# CPLD.net
KiCad netlist of a schematic drawn in Altium Designer
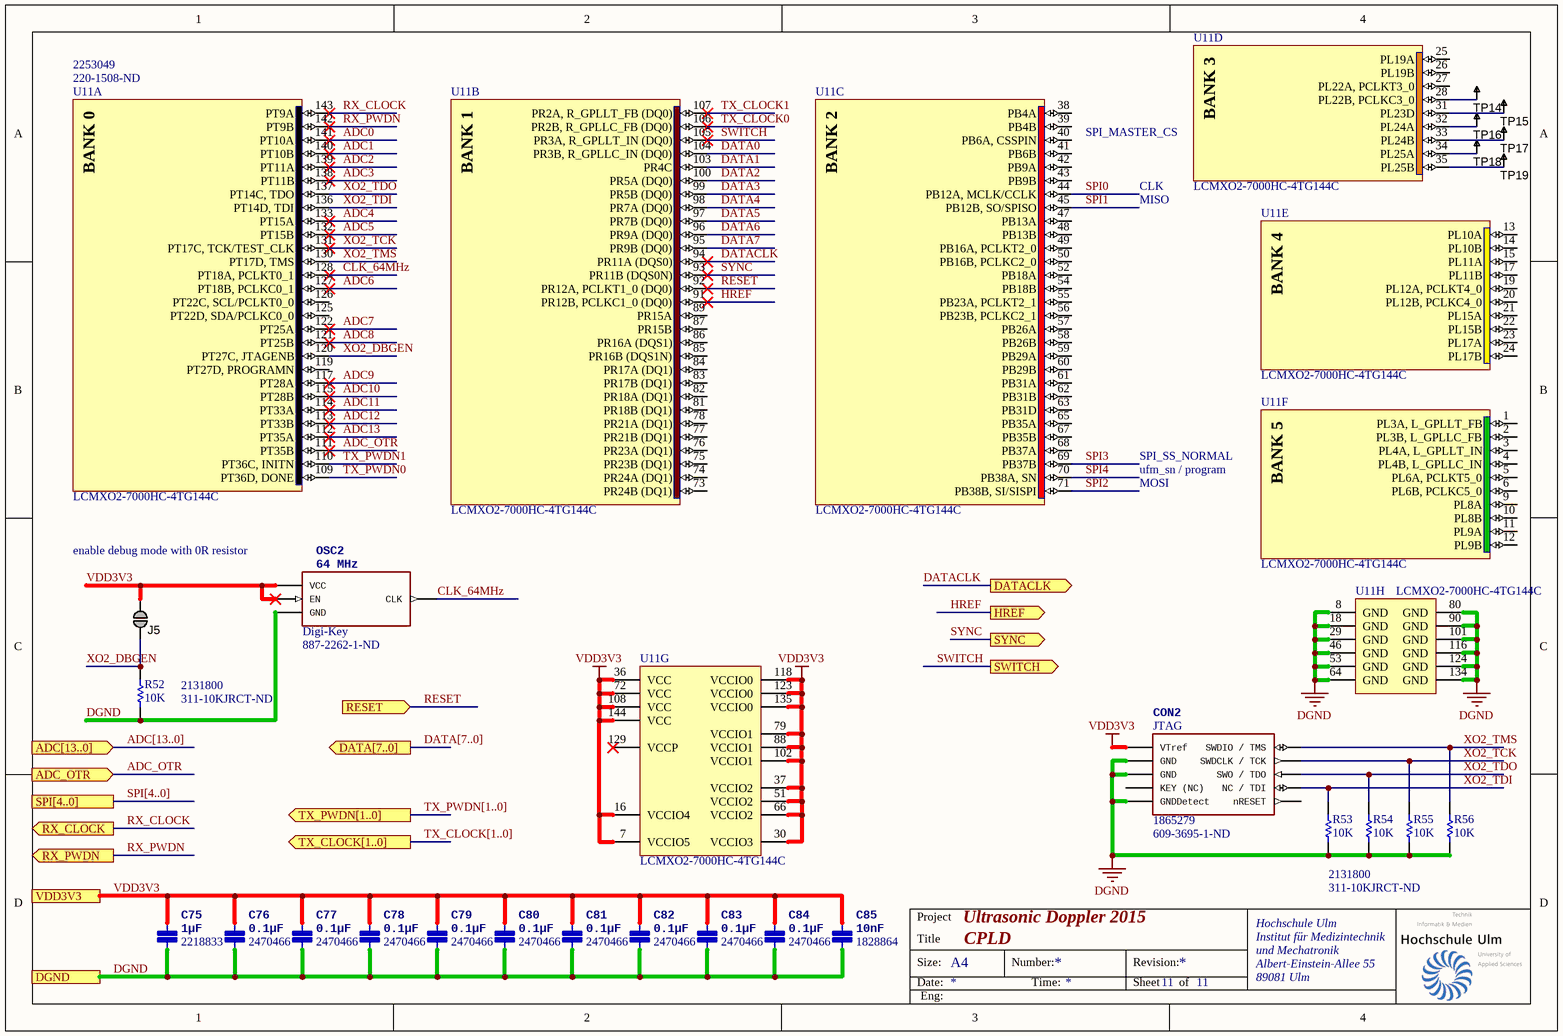
[diagram p0: CPLD.SchDoc]

(export (version "E")
  (design (tool "Eeschema 10.0.6"))
  (components
    (comp (ref "C75")
      (value "1µF")
      (footprint "0402[1005]")
      (description "Cap")
      (fields (field (name "SUPPLIER PART NUMBER 1") "2218833"))
      (libsource (lib "Components") (part "Capacitor"))
    )
    (comp (ref "C76")
      (value "0.1µF")
      (footprint "0402[1005]")
      (description "Cap")
      (fields (field (name "SUPPLIER PART NUMBER 1") "2470466"))
      (libsource (lib "Components") (part "Capacitor"))
    )
    (comp (ref "C77")
      (value "0.1µF")
      (footprint "0402[1005]")
      (description "Cap")
      (fields (field (name "SUPPLIER PART NUMBER 1") "2470466"))
      (libsource (lib "Components") (part "Capacitor"))
    )
    (comp (ref "C78")
      (value "0.1µF")
      (footprint "0402[1005]")
      (description "Cap")
      (fields (field (name "SUPPLIER PART NUMBER 1") "2470466"))
      (libsource (lib "Components") (part "Capacitor"))
    )
    (comp (ref "C79")
      (value "0.1µF")
      (footprint "0402[1005]")
      (description "Cap")
      (fields (field (name "SUPPLIER PART NUMBER 1") "2470466"))
      (libsource (lib "Components") (part "Capacitor"))
    )
    (comp (ref "C80")
      (value "0.1µF")
      (footprint "0402[1005]")
      (description "Cap")
      (fields (field (name "SUPPLIER PART NUMBER 1") "2470466"))
      (libsource (lib "Components") (part "Capacitor"))
    )
    (comp (ref "C81")
      (value "0.1µF")
      (footprint "0402[1005]")
      (description "Cap")
      (fields (field (name "SUPPLIER PART NUMBER 1") "2470466"))
      (libsource (lib "Components") (part "Capacitor"))
    )
    (comp (ref "C82")
      (value "0.1µF")
      (footprint "0402[1005]")
      (description "Cap")
      (fields (field (name "SUPPLIER PART NUMBER 1") "2470466"))
      (libsource (lib "Components") (part "Capacitor"))
    )
    (comp (ref "C83")
      (value "0.1µF")
      (footprint "0402[1005]")
      (description "Cap")
      (fields (field (name "SUPPLIER PART NUMBER 1") "2470466"))
      (libsource (lib "Components") (part "Capacitor"))
    )
    (comp (ref "C84")
      (value "0.1µF")
      (footprint "0402[1005]")
      (description "Cap")
      (fields (field (name "SUPPLIER PART NUMBER 1") "2470466"))
      (libsource (lib "Components") (part "Capacitor"))
    )
    (comp (ref "C85")
      (value "10nF")
      (footprint "0402[1005]")
      (description "Cap")
      (fields (field (name "SUPPLIER PART NUMBER 1") "1828864"))
      (libsource (lib "Components") (part "Capacitor"))
    )
    (comp (ref "CON2")
      (value "JTAG")
      (footprint "SWD-10-SMD")
      (fields
        (field (name "SUPPLIER PART NUMBER 1") "609-3695-1-ND")
        (field (name "SUPPLIER PART NUMBER 2") "1865279")
      )
      (libsource (lib "USD Parts") (part "SWD-10_SMD"))
    )
    (comp (ref "J5")
      (value "Jumper")
      (footprint "JUMP1")
      (description "SMD jumper")
      (libsource (lib "USD Parts") (part "JUMP1"))
    )
    (comp (ref "OSC2")
      (value "64 MHz")
      (footprint "3.2X.2.5")
      (description "Oszilator")
      (fields (field (name "SUPPLIER 1") "Digi-Key") (field (name "SUPPLIER PART NUMBER 1") "887-2262-1-ND"))
      (libsource (lib "USD Parts") (part "Crystal 4PIN"))
    )
    (comp (ref "R52")
      (value "10K")
      (footprint "0402[1005]")
      (description "Resistor")
      (fields
        (field (name "SUPPLIER PART NUMBER 1") "311-10KJRCT-ND")
        (field (name "SUPPLIER PART NUMBER 2") "2131800")
        (field (name "PUBLISHER") "Altium Limited")
      )
      (libsource (lib "USD Parts") (part "Resistor"))
    )
    (comp (ref "R53")
      (value "10K")
      (footprint "0402[1005]")
      (description "Resistor")
      (fields
        (field (name "SUPPLIER PART NUMBER 1") "311-10KJRCT-ND")
        (field (name "SUPPLIER PART NUMBER 2") "2131800")
        (field (name "PUBLISHER") "Altium Limited")
      )
      (libsource (lib "USD Parts") (part "Resistor"))
    )
    (comp (ref "R54")
      (value "10K")
      (footprint "0402[1005]")
      (description "Resistor")
      (fields (field (name "PUBLISHER") "Altium Limited"))
      (libsource (lib "USD Parts") (part "Resistor"))
    )
    (comp (ref "R55")
      (value "10K")
      (footprint "0402[1005]")
      (description "Resistor")
      (fields (field (name "PUBLISHER") "Altium Limited"))
      (libsource (lib "USD Parts") (part "Resistor"))
    )
    (comp (ref "R56")
      (value "10K")
      (footprint "0402[1005]")
      (description "Resistor")
      (fields (field (name "PUBLISHER") "Altium Limited"))
      (libsource (lib "USD Parts") (part "Resistor"))
    )
    (comp (ref "TP14")
      (value "TESTPOINT_THT_MINI")
      (footprint "TP-THT-MINI")
      (description "Test Point PCB mount Miniature White")
      (fields (field (name "PBL PART NUMBER") "3100-567"))
      (libsource (lib "USD Parts") (part "TESTPOINT_THT_MINI"))
    )
    (comp (ref "TP15")
      (value "TESTPOINT_THT_MINI")
      (footprint "TP-THT-MINI")
      (description "Test Point PCB mount Miniature White")
      (fields (field (name "PBL PART NUMBER") "3100-567"))
      (libsource (lib "USD Parts") (part "TESTPOINT_THT_MINI"))
    )
    (comp (ref "TP16")
      (value "TESTPOINT_THT_MINI")
      (footprint "TP-THT-MINI")
      (description "Test Point PCB mount Miniature White")
      (fields (field (name "PBL PART NUMBER") "3100-567"))
      (libsource (lib "USD Parts") (part "TESTPOINT_THT_MINI"))
    )
    (comp (ref "TP17")
      (value "TESTPOINT_THT_MINI")
      (footprint "TP-THT-MINI")
      (description "Test Point PCB mount Miniature White")
      (fields (field (name "PBL PART NUMBER") "3100-567"))
      (libsource (lib "USD Parts") (part "TESTPOINT_THT_MINI"))
    )
    (comp (ref "TP18")
      (value "TESTPOINT_THT_MINI")
      (footprint "TP-THT-MINI")
      (description "Test Point PCB mount Miniature White")
      (fields (field (name "PBL PART NUMBER") "3100-567"))
      (libsource (lib "USD Parts") (part "TESTPOINT_THT_MINI"))
    )
    (comp (ref "TP19")
      (value "TESTPOINT_THT_MINI")
      (footprint "TP-THT-MINI")
      (description "Test Point PCB mount Miniature White")
      (fields (field (name "PBL PART NUMBER") "3100-567"))
      (libsource (lib "USD Parts") (part "TESTPOINT_THT_MINI"))
    )
    (comp (ref "U11")
      (value "LCMXO2-7000HC-4TG144C")
      (footprint "TQFP144_N")
      (fields
        (field (name "SUPPLIER PART NUMBER 1") "220-1508-ND")
        (field (name "SUPPLIER PART NUMBER 2") "2253049")
      )
      (libsource (lib "Altium Content Vault") (part "PLD-LTMXO2-7000-TQ144"))
    )
  )
  (nets
    (net (code "1") (name "/ADC0") (class "Default")
      (node (ref "U11") (pin "141") (pinfunction "PT10A_141") (pintype "bidirectional+no_connect"))
    )
    (net (code "2") (name "/ADC1") (class "Default")
      (node (ref "U11") (pin "140") (pinfunction "PT10B_140") (pintype "bidirectional+no_connect"))
    )
    (net (code "3") (name "/ADC2") (class "Default")
      (node (ref "U11") (pin "139") (pinfunction "PT11A_139") (pintype "bidirectional+no_connect"))
    )
    (net (code "4") (name "/ADC3") (class "Default")
      (node (ref "U11") (pin "138") (pinfunction "PT11B_138") (pintype "bidirectional+no_connect"))
    )
    (net (code "5") (name "/ADC4") (class "Default")
      (node (ref "U11") (pin "133") (pinfunction "PT15A_133") (pintype "bidirectional+no_connect"))
    )
    (net (code "6") (name "/ADC5") (class "Default")
      (node (ref "U11") (pin "132") (pinfunction "PT15B_132") (pintype "bidirectional+no_connect"))
    )
    (net (code "7") (name "/ADC6") (class "Default")
      (node (ref "U11") (pin "127") (pinfunction "PT18B,_PCLKC0_1_127") (pintype "bidirectional+no_connect"))
    )
    (net (code "8") (name "/ADC7") (class "Default")
      (node (ref "U11") (pin "122") (pinfunction "PT25A_122") (pintype "bidirectional+no_connect"))
    )
    (net (code "9") (name "/ADC8") (class "Default")
      (node (ref "U11") (pin "121") (pinfunction "PT25B_121") (pintype "bidirectional+no_connect"))
    )
    (net (code "10") (name "/ADC9") (class "Default")
      (node (ref "U11") (pin "117") (pinfunction "PT28A_117") (pintype "bidirectional+no_connect"))
    )
    (net (code "11") (name "/ADC10") (class "Default")
      (node (ref "U11") (pin "115") (pinfunction "PT28B_115") (pintype "bidirectional+no_connect"))
    )
    (net (code "12") (name "/ADC11") (class "Default")
      (node (ref "U11") (pin "114") (pinfunction "PT33A_114") (pintype "bidirectional+no_connect"))
    )
    (net (code "13") (name "/ADC12") (class "Default")
      (node (ref "U11") (pin "113") (pinfunction "PT33B_113") (pintype "bidirectional+no_connect"))
    )
    (net (code "14") (name "/ADC13") (class "Default")
      (node (ref "U11") (pin "112") (pinfunction "PT35A_112") (pintype "bidirectional+no_connect"))
    )
    (net (code "16") (name "/ADC_OTR") (class "Default")
      (node (ref "U11") (pin "111") (pinfunction "PT35B_111") (pintype "bidirectional"))
    )
    (net (code "17") (name "/CLK_64MHz") (class "Default")
      (node (ref "OSC2") (pin "CLK") (pinfunction "CLK_CLK") (pintype "output"))
      (node (ref "U11") (pin "128") (pinfunction "PT18A,_PCLKT0_1_128") (pintype "bidirectional"))
    )
    (net (code "18") (name "/DATA0") (class "Default")
      (node (ref "U11") (pin "104") (pinfunction "PR3B,_R_GPLLC_IN_(DQ0)_104") (pintype "bidirectional"))
    )
    (net (code "19") (name "/DATA1") (class "Default")
      (node (ref "U11") (pin "103") (pinfunction "PR4C_103") (pintype "bidirectional"))
    )
    (net (code "20") (name "/DATA2") (class "Default")
      (node (ref "U11") (pin "100") (pinfunction "PR5A_(DQ0)_100") (pintype "bidirectional"))
    )
    (net (code "21") (name "/DATA3") (class "Default")
      (node (ref "U11") (pin "99") (pinfunction "PR5B_(DQ0)_99") (pintype "bidirectional"))
    )
    (net (code "22") (name "/DATA4") (class "Default")
      (node (ref "U11") (pin "98") (pinfunction "PR7A_(DQ0)_98") (pintype "bidirectional"))
    )
    (net (code "23") (name "/DATA5") (class "Default")
      (node (ref "U11") (pin "97") (pinfunction "PR7B_(DQ0)_97") (pintype "bidirectional"))
    )
    (net (code "24") (name "/DATA6") (class "Default")
      (node (ref "U11") (pin "96") (pinfunction "PR9A_(DQ0)_96") (pintype "bidirectional"))
    )
    (net (code "25") (name "/DATA7") (class "Default")
      (node (ref "U11") (pin "95") (pinfunction "PR9B_(DQ0)_95") (pintype "bidirectional"))
    )
    (net (code "26") (name "/DATACLK") (class "Default")
      (node (ref "U11") (pin "94") (pinfunction "PR11A_(DQS0)_94") (pintype "bidirectional+no_connect"))
    )
    (net (code "28") (name "/HREF") (class "Default")
      (node (ref "U11") (pin "91") (pinfunction "PR12B,_PCLKC1_0_(DQ0)_91") (pintype "bidirectional+no_connect"))
    )
    (net (code "29") (name "/RESET") (class "Default")
      (node (ref "U11") (pin "92") (pinfunction "PR12A,_PCLKT1_0_(DQ0)_92") (pintype "bidirectional+no_connect"))
    )
    (net (code "30") (name "/RX_CLOCK") (class "Default")
      (node (ref "U11") (pin "143") (pinfunction "PT9A_143") (pintype "bidirectional+no_connect"))
    )
    (net (code "31") (name "/RX_PWDN") (class "Default")
      (node (ref "U11") (pin "142") (pinfunction "PT9B_142") (pintype "bidirectional+no_connect"))
    )
    (net (code "32") (name "/SPI0") (class "Default")
      (node (ref "U11") (pin "44") (pinfunction "PB12A,_MCLK/CCLK_44") (pintype "bidirectional"))
    )
    (net (code "33") (name "/SPI1") (class "Default")
      (node (ref "U11") (pin "45") (pinfunction "PB12B,_SO/SPISO_45") (pintype "bidirectional"))
    )
    (net (code "34") (name "/SPI2") (class "Default")
      (node (ref "U11") (pin "71") (pinfunction "PB38B,_SI/SISPI_71") (pintype "bidirectional"))
    )
    (net (code "35") (name "/SPI3") (class "Default")
      (node (ref "U11") (pin "69") (pinfunction "PB37B_69") (pintype "bidirectional"))
    )
    (net (code "36") (name "/SPI4") (class "Default")
      (node (ref "U11") (pin "70") (pinfunction "PB38A,_SN_70") (pintype "bidirectional"))
    )
    (net (code "38") (name "/SWITCH") (class "Default")
      (node (ref "U11") (pin "105") (pinfunction "PR3A,_R_GPLLT_IN_(DQ0)_105") (pintype "bidirectional+no_connect"))
    )
    (net (code "39") (name "/SYNC") (class "Default")
      (node (ref "U11") (pin "93") (pinfunction "PR11B_(DQS0N)_93") (pintype "bidirectional+no_connect"))
    )
    (net (code "40") (name "/TX_CLOCK0") (class "Default")
      (node (ref "U11") (pin "106") (pinfunction "PR2B,_R_GPLLC_FB_(DQ0)_106") (pintype "bidirectional+no_connect"))
    )
    (net (code "41") (name "/TX_CLOCK1") (class "Default")
      (node (ref "U11") (pin "107") (pinfunction "PR2A,_R_GPLLT_FB_(DQ0)_107") (pintype "bidirectional+no_connect"))
    )
    (net (code "43") (name "/TX_PWDN0") (class "Default")
      (node (ref "U11") (pin "109") (pinfunction "PT36D,_DONE_109") (pintype "bidirectional"))
    )
    (net (code "44") (name "/TX_PWDN1") (class "Default")
      (node (ref "U11") (pin "110") (pinfunction "PT36C,_INITN_110") (pintype "bidirectional"))
    )
    (net (code "46") (name "/XO2_DBGEN") (class "Default")
      (node (ref "J5") (pin "2") (pintype "passive"))
      (node (ref "R52") (pin "2") (pinfunction "2_2") (pintype "passive"))
      (node (ref "U11") (pin "120") (pinfunction "PT27C,_JTAGENB_120") (pintype "bidirectional"))
    )
    (net (code "47") (name "/XO2_TCK") (class "Default")
      (node (ref "CON2") (pin "TCK") (pinfunction "SWDCLK_/_TCK_TCK") (pintype "output"))
      (node (ref "R55") (pin "1") (pinfunction "1_1") (pintype "passive"))
      (node (ref "U11") (pin "131") (pinfunction "PT17C,_TCK/TEST_CLK_131") (pintype "bidirectional"))
    )
    (net (code "48") (name "/XO2_TDI") (class "Default")
      (node (ref "CON2") (pin "TDI") (pinfunction "NC_/_TDI_TDI") (pintype "bidirectional"))
      (node (ref "R53") (pin "1") (pinfunction "1_1") (pintype "passive"))
      (node (ref "U11") (pin "136") (pinfunction "PT14D,_TDI_136") (pintype "bidirectional"))
    )
    (net (code "49") (name "/XO2_TDO") (class "Default")
      (node (ref "CON2") (pin "TDO") (pinfunction "SWO_/_TDO_TDO") (pintype "input"))
      (node (ref "R54") (pin "1") (pinfunction "1_1") (pintype "passive"))
      (node (ref "U11") (pin "137") (pinfunction "PT14C,_TDO_137") (pintype "bidirectional"))
    )
    (net (code "50") (name "/XO2_TMS") (class "Default")
      (node (ref "CON2") (pin "TMS") (pinfunction "SWDIO_/_TMS_TMS") (pintype "bidirectional"))
      (node (ref "R56") (pin "1") (pinfunction "1_1") (pintype "passive"))
      (node (ref "U11") (pin "130") (pinfunction "PT17D,_TMS_130") (pintype "bidirectional"))
    )
    (net (code "51") (name "DGND") (class "Default")
      (node (ref "C75") (pin "2") (pinfunction "P$2_2") (pintype "passive"))
      (node (ref "C76") (pin "2") (pinfunction "P$2_2") (pintype "passive"))
      (node (ref "C77") (pin "2") (pinfunction "P$2_2") (pintype "passive"))
      (node (ref "C78") (pin "2") (pinfunction "P$2_2") (pintype "passive"))
      (node (ref "C79") (pin "2") (pinfunction "P$2_2") (pintype "passive"))
      (node (ref "C80") (pin "2") (pinfunction "P$2_2") (pintype "passive"))
      (node (ref "C81") (pin "2") (pinfunction "P$2_2") (pintype "passive"))
      (node (ref "C82") (pin "2") (pinfunction "P$2_2") (pintype "passive"))
      (node (ref "C83") (pin "2") (pinfunction "P$2_2") (pintype "passive"))
      (node (ref "C84") (pin "2") (pinfunction "P$2_2") (pintype "passive"))
      (node (ref "C85") (pin "2") (pinfunction "P$2_2") (pintype "passive"))
      (node (ref "CON2") (pin "GND") (pinfunction "GND_GND") (pintype "passive"))
      (node (ref "CON2") (pin "GNDDetect") (pinfunction "GNDDetect_GNDDetect") (pintype "passive"))
      (node (ref "OSC2") (pin "GND") (pinfunction "GND_GND") (pintype "power_in"))
      (node (ref "R52") (pin "1") (pinfunction "1_1") (pintype "passive"))
      (node (ref "R53") (pin "2") (pinfunction "2_2") (pintype "passive"))
      (node (ref "R54") (pin "2") (pinfunction "2_2") (pintype "passive"))
      (node (ref "R55") (pin "2") (pinfunction "2_2") (pintype "passive"))
      (node (ref "R56") (pin "2") (pinfunction "2_2") (pintype "passive"))
      (node (ref "U11") (pin "101") (pinfunction "GND_101") (pintype "power_in"))
      (node (ref "U11") (pin "116") (pinfunction "GND_116") (pintype "power_in"))
      (node (ref "U11") (pin "124") (pinfunction "GND_124") (pintype "power_in"))
      (node (ref "U11") (pin "134") (pinfunction "GND_134") (pintype "power_in"))
      (node (ref "U11") (pin "18") (pinfunction "GND_18") (pintype "power_in"))
      (node (ref "U11") (pin "29") (pinfunction "GND_29") (pintype "power_in"))
      (node (ref "U11") (pin "46") (pinfunction "GND_46") (pintype "power_in"))
      (node (ref "U11") (pin "53") (pinfunction "GND_53") (pintype "power_in"))
      (node (ref "U11") (pin "64") (pinfunction "GND_64") (pintype "power_in"))
      (node (ref "U11") (pin "8") (pinfunction "GND_8") (pintype "power_in"))
      (node (ref "U11") (pin "80") (pinfunction "GND_80") (pintype "power_in"))
      (node (ref "U11") (pin "90") (pinfunction "GND_90") (pintype "power_in"))
    )
    (net (code "52") (name "Net-(U11D-PL22B,_PCLKC3_0)") (class "Default")
      (node (ref "TP14") (pin "1") (pintype "passive"))
      (node (ref "U11") (pin "28") (pinfunction "PL22B,_PCLKC3_0_28") (pintype "bidirectional"))
    )
    (net (code "53") (name "Net-(U11D-PL23D)") (class "Default")
      (node (ref "TP15") (pin "1") (pintype "passive"))
      (node (ref "U11") (pin "31") (pinfunction "PL23D_31") (pintype "bidirectional"))
    )
    (net (code "54") (name "Net-(U11D-PL24A)") (class "Default")
      (node (ref "TP16") (pin "1") (pintype "passive"))
      (node (ref "U11") (pin "32") (pinfunction "PL24A_32") (pintype "bidirectional"))
    )
    (net (code "55") (name "Net-(U11D-PL24B)") (class "Default")
      (node (ref "TP17") (pin "1") (pintype "passive"))
      (node (ref "U11") (pin "33") (pinfunction "PL24B_33") (pintype "bidirectional"))
    )
    (net (code "56") (name "Net-(U11D-PL25A)") (class "Default")
      (node (ref "TP18") (pin "1") (pintype "passive"))
      (node (ref "U11") (pin "34") (pinfunction "PL25A_34") (pintype "bidirectional"))
    )
    (net (code "57") (name "Net-(U11D-PL25B)") (class "Default")
      (node (ref "TP19") (pin "1") (pintype "passive"))
      (node (ref "U11") (pin "35") (pinfunction "PL25B_35") (pintype "bidirectional"))
    )
    (net (code "58") (name "VDD3V3") (class "Default")
      (node (ref "C75") (pin "1") (pinfunction "P$1_1") (pintype "passive"))
      (node (ref "C76") (pin "1") (pinfunction "P$1_1") (pintype "passive"))
      (node (ref "C77") (pin "1") (pinfunction "P$1_1") (pintype "passive"))
      (node (ref "C78") (pin "1") (pinfunction "P$1_1") (pintype "passive"))
      (node (ref "C79") (pin "1") (pinfunction "P$1_1") (pintype "passive"))
      (node (ref "C80") (pin "1") (pinfunction "P$1_1") (pintype "passive"))
      (node (ref "C81") (pin "1") (pinfunction "P$1_1") (pintype "passive"))
      (node (ref "C82") (pin "1") (pinfunction "P$1_1") (pintype "passive"))
      (node (ref "C83") (pin "1") (pinfunction "P$1_1") (pintype "passive"))
      (node (ref "C84") (pin "1") (pinfunction "P$1_1") (pintype "passive"))
      (node (ref "C85") (pin "1") (pinfunction "P$1_1") (pintype "passive"))
      (node (ref "CON2") (pin "VTref") (pinfunction "VTref_VTref") (pintype "passive"))
      (node (ref "J5") (pin "1") (pintype "passive"))
      (node (ref "OSC2") (pin "EN") (pinfunction "EN_EN") (pintype "input"))
      (node (ref "OSC2") (pin "VCC") (pinfunction "VCC_VCC") (pintype "power_in"))
      (node (ref "U11") (pin "102") (pinfunction "VCCIO1_102") (pintype "power_in"))
      (node (ref "U11") (pin "108") (pinfunction "VCC_108") (pintype "power_in"))
      (node (ref "U11") (pin "118") (pinfunction "VCCIO0_118") (pintype "power_in"))
      (node (ref "U11") (pin "123") (pinfunction "VCCIO0_123") (pintype "power_in"))
      (node (ref "U11") (pin "135") (pinfunction "VCCIO0_135") (pintype "power_in"))
      (node (ref "U11") (pin "144") (pinfunction "VCC_144") (pintype "power_in"))
      (node (ref "U11") (pin "16") (pinfunction "VCCIO4_16") (pintype "power_in"))
      (node (ref "U11") (pin "30") (pinfunction "VCCIO3_30") (pintype "power_in"))
      (node (ref "U11") (pin "36") (pinfunction "VCC_36") (pintype "power_in"))
      (node (ref "U11") (pin "37") (pinfunction "VCCIO2_37") (pintype "power_in"))
      (node (ref "U11") (pin "51") (pinfunction "VCCIO2_51") (pintype "power_in"))
      (node (ref "U11") (pin "66") (pinfunction "VCCIO2_66") (pintype "power_in"))
      (node (ref "U11") (pin "7") (pinfunction "VCCIO5_7") (pintype "power_in"))
      (node (ref "U11") (pin "72") (pinfunction "VCC_72") (pintype "power_in"))
      (node (ref "U11") (pin "79") (pinfunction "VCCIO1_79") (pintype "power_in"))
      (node (ref "U11") (pin "88") (pinfunction "VCCIO1_88") (pintype "power_in"))
    )
    (net (code "59") (name "unconnected-(CON2-KEY_(NC)-PadKEY)") (class "Default")
      (node (ref "CON2") (pin "KEY") (pinfunction "KEY_(NC)_KEY") (pintype "passive"))
    )
    (net (code "60") (name "unconnected-(CON2-PadnRESET)") (class "Default")
      (node (ref "CON2") (pin "nRESET") (pinfunction "nRESET_nRESET") (pintype "output"))
    )
    (net (code "61") (name "unconnected-(U11A-PT22C,_SCL{slash}PCLKT0_0-Pad126)") (class "Default")
      (node (ref "U11") (pin "126") (pinfunction "PT22C,_SCL/PCLKT0_0_126") (pintype "bidirectional"))
    )
    (net (code "62") (name "unconnected-(U11A-PT22D,_SDA{slash}PCLKC0_0-Pad125)") (class "Default")
      (node (ref "U11") (pin "125") (pinfunction "PT22D,_SDA/PCLKC0_0_125") (pintype "bidirectional"))
    )
    (net (code "63") (name "unconnected-(U11A-PT27D,_PROGRAMN-Pad119)") (class "Default")
      (node (ref "U11") (pin "119") (pinfunction "PT27D,_PROGRAMN_119") (pintype "bidirectional"))
    )
    (net (code "64") (name "unconnected-(U11B-PR15A-Pad89)") (class "Default")
      (node (ref "U11") (pin "89") (pinfunction "PR15A_89") (pintype "bidirectional"))
    )
    (net (code "65") (name "unconnected-(U11B-PR15B-Pad87)") (class "Default")
      (node (ref "U11") (pin "87") (pinfunction "PR15B_87") (pintype "bidirectional"))
    )
    (net (code "66") (name "unconnected-(U11B-PR16A_(DQS1)-Pad86)") (class "Default")
      (node (ref "U11") (pin "86") (pinfunction "PR16A_(DQS1)_86") (pintype "bidirectional"))
    )
    (net (code "67") (name "unconnected-(U11B-PR16B_(DQS1N)-Pad85)") (class "Default")
      (node (ref "U11") (pin "85") (pinfunction "PR16B_(DQS1N)_85") (pintype "bidirectional"))
    )
    (net (code "68") (name "unconnected-(U11B-PR17A_(DQ1)-Pad84)") (class "Default")
      (node (ref "U11") (pin "84") (pinfunction "PR17A_(DQ1)_84") (pintype "bidirectional"))
    )
    (net (code "69") (name "unconnected-(U11B-PR17B_(DQ1)-Pad83)") (class "Default")
      (node (ref "U11") (pin "83") (pinfunction "PR17B_(DQ1)_83") (pintype "bidirectional"))
    )
    (net (code "70") (name "unconnected-(U11B-PR18A_(DQ1)-Pad82)") (class "Default")
      (node (ref "U11") (pin "82") (pinfunction "PR18A_(DQ1)_82") (pintype "bidirectional"))
    )
    (net (code "71") (name "unconnected-(U11B-PR18B_(DQ1)-Pad81)") (class "Default")
      (node (ref "U11") (pin "81") (pinfunction "PR18B_(DQ1)_81") (pintype "bidirectional"))
    )
    (net (code "72") (name "unconnected-(U11B-PR21A_(DQ1)-Pad78)") (class "Default")
      (node (ref "U11") (pin "78") (pinfunction "PR21A_(DQ1)_78") (pintype "bidirectional"))
    )
    (net (code "73") (name "unconnected-(U11B-PR21B_(DQ1)-Pad77)") (class "Default")
      (node (ref "U11") (pin "77") (pinfunction "PR21B_(DQ1)_77") (pintype "bidirectional"))
    )
    (net (code "74") (name "unconnected-(U11B-PR23A_(DQ1)-Pad76)") (class "Default")
      (node (ref "U11") (pin "76") (pinfunction "PR23A_(DQ1)_76") (pintype "bidirectional"))
    )
    (net (code "75") (name "unconnected-(U11B-PR23B_(DQ1)-Pad75)") (class "Default")
      (node (ref "U11") (pin "75") (pinfunction "PR23B_(DQ1)_75") (pintype "bidirectional"))
    )
    (net (code "76") (name "unconnected-(U11B-PR24A_(DQ1)-Pad74)") (class "Default")
      (node (ref "U11") (pin "74") (pinfunction "PR24A_(DQ1)_74") (pintype "bidirectional"))
    )
    (net (code "77") (name "unconnected-(U11B-PR24B_(DQ1)-Pad73)") (class "Default")
      (node (ref "U11") (pin "73") (pinfunction "PR24B_(DQ1)_73") (pintype "bidirectional"))
    )
    (net (code "78") (name "unconnected-(U11C-PB4A-Pad38)") (class "Default")
      (node (ref "U11") (pin "38") (pinfunction "PB4A_38") (pintype "bidirectional"))
    )
    (net (code "79") (name "unconnected-(U11C-PB4B-Pad39)") (class "Default")
      (node (ref "U11") (pin "39") (pinfunction "PB4B_39") (pintype "bidirectional"))
    )
    (net (code "80") (name "unconnected-(U11C-PB6A,_CSSPIN-Pad40)") (class "Default")
      (node (ref "U11") (pin "40") (pinfunction "PB6A,_CSSPIN_40") (pintype "bidirectional"))
    )
    (net (code "81") (name "unconnected-(U11C-PB6B-Pad41)") (class "Default")
      (node (ref "U11") (pin "41") (pinfunction "PB6B_41") (pintype "bidirectional"))
    )
    (net (code "82") (name "unconnected-(U11C-PB9A-Pad42)") (class "Default")
      (node (ref "U11") (pin "42") (pinfunction "PB9A_42") (pintype "bidirectional"))
    )
    (net (code "83") (name "unconnected-(U11C-PB9B-Pad43)") (class "Default")
      (node (ref "U11") (pin "43") (pinfunction "PB9B_43") (pintype "bidirectional"))
    )
    (net (code "84") (name "unconnected-(U11C-PB13A-Pad47)") (class "Default")
      (node (ref "U11") (pin "47") (pinfunction "PB13A_47") (pintype "bidirectional"))
    )
    (net (code "85") (name "unconnected-(U11C-PB13B-Pad48)") (class "Default")
      (node (ref "U11") (pin "48") (pinfunction "PB13B_48") (pintype "bidirectional"))
    )
    (net (code "86") (name "unconnected-(U11C-PB16A,_PCLKT2_0-Pad49)") (class "Default")
      (node (ref "U11") (pin "49") (pinfunction "PB16A,_PCLKT2_0_49") (pintype "bidirectional"))
    )
    (net (code "87") (name "unconnected-(U11C-PB16B,_PCLKC2_0-Pad50)") (class "Default")
      (node (ref "U11") (pin "50") (pinfunction "PB16B,_PCLKC2_0_50") (pintype "bidirectional"))
    )
    (net (code "88") (name "unconnected-(U11C-PB18A-Pad52)") (class "Default")
      (node (ref "U11") (pin "52") (pinfunction "PB18A_52") (pintype "bidirectional"))
    )
    (net (code "89") (name "unconnected-(U11C-PB18B-Pad54)") (class "Default")
      (node (ref "U11") (pin "54") (pinfunction "PB18B_54") (pintype "bidirectional"))
    )
    (net (code "90") (name "unconnected-(U11C-PB23A,_PCLKT2_1-Pad55)") (class "Default")
      (node (ref "U11") (pin "55") (pinfunction "PB23A,_PCLKT2_1_55") (pintype "bidirectional"))
    )
    (net (code "91") (name "unconnected-(U11C-PB23B,_PCLKC2_1-Pad56)") (class "Default")
      (node (ref "U11") (pin "56") (pinfunction "PB23B,_PCLKC2_1_56") (pintype "bidirectional"))
    )
    (net (code "92") (name "unconnected-(U11C-PB26A-Pad57)") (class "Default")
      (node (ref "U11") (pin "57") (pinfunction "PB26A_57") (pintype "bidirectional"))
    )
    (net (code "93") (name "unconnected-(U11C-PB26B-Pad58)") (class "Default")
      (node (ref "U11") (pin "58") (pinfunction "PB26B_58") (pintype "bidirectional"))
    )
    (net (code "94") (name "unconnected-(U11C-PB29A-Pad59)") (class "Default")
      (node (ref "U11") (pin "59") (pinfunction "PB29A_59") (pintype "bidirectional"))
    )
    (net (code "95") (name "unconnected-(U11C-PB29B-Pad60)") (class "Default")
      (node (ref "U11") (pin "60") (pinfunction "PB29B_60") (pintype "bidirectional"))
    )
    (net (code "96") (name "unconnected-(U11C-PB31A-Pad61)") (class "Default")
      (node (ref "U11") (pin "61") (pinfunction "PB31A_61") (pintype "bidirectional"))
    )
    (net (code "97") (name "unconnected-(U11C-PB31B-Pad62)") (class "Default")
      (node (ref "U11") (pin "62") (pinfunction "PB31B_62") (pintype "bidirectional"))
    )
    (net (code "98") (name "unconnected-(U11C-PB31D-Pad63)") (class "Default")
      (node (ref "U11") (pin "63") (pinfunction "PB31D_63") (pintype "bidirectional"))
    )
    (net (code "99") (name "unconnected-(U11C-PB35A-Pad65)") (class "Default")
      (node (ref "U11") (pin "65") (pinfunction "PB35A_65") (pintype "bidirectional"))
    )
    (net (code "100") (name "unconnected-(U11C-PB35B-Pad67)") (class "Default")
      (node (ref "U11") (pin "67") (pinfunction "PB35B_67") (pintype "bidirectional"))
    )
    (net (code "101") (name "unconnected-(U11C-PB37A-Pad68)") (class "Default")
      (node (ref "U11") (pin "68") (pinfunction "PB37A_68") (pintype "bidirectional"))
    )
    (net (code "102") (name "unconnected-(U11D-PL19A-Pad25)") (class "Default")
      (node (ref "U11") (pin "25") (pinfunction "PL19A_25") (pintype "bidirectional"))
    )
    (net (code "103") (name "unconnected-(U11D-PL19B-Pad26)") (class "Default")
      (node (ref "U11") (pin "26") (pinfunction "PL19B_26") (pintype "bidirectional"))
    )
    (net (code "104") (name "unconnected-(U11D-PL22A,_PCLKT3_0-Pad27)") (class "Default")
      (node (ref "U11") (pin "27") (pinfunction "PL22A,_PCLKT3_0_27") (pintype "bidirectional"))
    )
    (net (code "105") (name "unconnected-(U11E-PL10A-Pad13)") (class "Default")
      (node (ref "U11") (pin "13") (pinfunction "PL10A_13") (pintype "bidirectional"))
    )
    (net (code "106") (name "unconnected-(U11E-PL10B-Pad14)") (class "Default")
      (node (ref "U11") (pin "14") (pinfunction "PL10B_14") (pintype "bidirectional"))
    )
    (net (code "107") (name "unconnected-(U11E-PL11A-Pad15)") (class "Default")
      (node (ref "U11") (pin "15") (pinfunction "PL11A_15") (pintype "bidirectional"))
    )
    (net (code "108") (name "unconnected-(U11E-PL11B-Pad17)") (class "Default")
      (node (ref "U11") (pin "17") (pinfunction "PL11B_17") (pintype "bidirectional"))
    )
    (net (code "109") (name "unconnected-(U11E-PL12A,_PCLKT4_0-Pad19)") (class "Default")
      (node (ref "U11") (pin "19") (pinfunction "PL12A,_PCLKT4_0_19") (pintype "bidirectional"))
    )
    (net (code "110") (name "unconnected-(U11E-PL12B,_PCLKC4_0-Pad20)") (class "Default")
      (node (ref "U11") (pin "20") (pinfunction "PL12B,_PCLKC4_0_20") (pintype "bidirectional"))
    )
    (net (code "111") (name "unconnected-(U11E-PL15A-Pad21)") (class "Default")
      (node (ref "U11") (pin "21") (pinfunction "PL15A_21") (pintype "bidirectional"))
    )
    (net (code "112") (name "unconnected-(U11E-PL15B-Pad22)") (class "Default")
      (node (ref "U11") (pin "22") (pinfunction "PL15B_22") (pintype "bidirectional"))
    )
    (net (code "113") (name "unconnected-(U11E-PL17A-Pad23)") (class "Default")
      (node (ref "U11") (pin "23") (pinfunction "PL17A_23") (pintype "bidirectional"))
    )
    (net (code "114") (name "unconnected-(U11E-PL17B-Pad24)") (class "Default")
      (node (ref "U11") (pin "24") (pinfunction "PL17B_24") (pintype "bidirectional"))
    )
    (net (code "115") (name "unconnected-(U11F-PL3A,_L_GPLLT_FB-Pad1)") (class "Default")
      (node (ref "U11") (pin "1") (pinfunction "PL3A,_L_GPLLT_FB_1") (pintype "bidirectional"))
    )
    (net (code "116") (name "unconnected-(U11F-PL3B,_L_GPLLC_FB-Pad2)") (class "Default")
      (node (ref "U11") (pin "2") (pinfunction "PL3B,_L_GPLLC_FB_2") (pintype "bidirectional"))
    )
    (net (code "117") (name "unconnected-(U11F-PL4A,_L_GPLLT_IN-Pad3)") (class "Default")
      (node (ref "U11") (pin "3") (pinfunction "PL4A,_L_GPLLT_IN_3") (pintype "bidirectional"))
    )
    (net (code "118") (name "unconnected-(U11F-PL4B,_L_GPLLC_IN-Pad4)") (class "Default")
      (node (ref "U11") (pin "4") (pinfunction "PL4B,_L_GPLLC_IN_4") (pintype "bidirectional"))
    )
    (net (code "119") (name "unconnected-(U11F-PL6A,_PCLKT5_0-Pad5)") (class "Default")
      (node (ref "U11") (pin "5") (pinfunction "PL6A,_PCLKT5_0_5") (pintype "bidirectional"))
    )
    (net (code "120") (name "unconnected-(U11F-PL6B,_PCLKC5_0-Pad6)") (class "Default")
      (node (ref "U11") (pin "6") (pinfunction "PL6B,_PCLKC5_0_6") (pintype "bidirectional"))
    )
    (net (code "121") (name "unconnected-(U11F-PL8A-Pad9)") (class "Default")
      (node (ref "U11") (pin "9") (pinfunction "PL8A_9") (pintype "bidirectional"))
    )
    (net (code "122") (name "unconnected-(U11F-PL8B-Pad10)") (class "Default")
      (node (ref "U11") (pin "10") (pinfunction "PL8B_10") (pintype "bidirectional"))
    )
    (net (code "123") (name "unconnected-(U11F-PL9A-Pad11)") (class "Default")
      (node (ref "U11") (pin "11") (pinfunction "PL9A_11") (pintype "bidirectional"))
    )
    (net (code "124") (name "unconnected-(U11F-PL9B-Pad12)") (class "Default")
      (node (ref "U11") (pin "12") (pinfunction "PL9B_12") (pintype "bidirectional"))
    )
    (net (code "125") (name "unconnected-(U11G-VCCP-Pad129)") (class "Default")
      (node (ref "U11") (pin "129") (pinfunction "VCCP_129") (pintype "power_in+no_connect"))
    )
  )
)
